# DoublePN-11092017-001.net
KiCad netlist of a schematic drawn in EAGLE
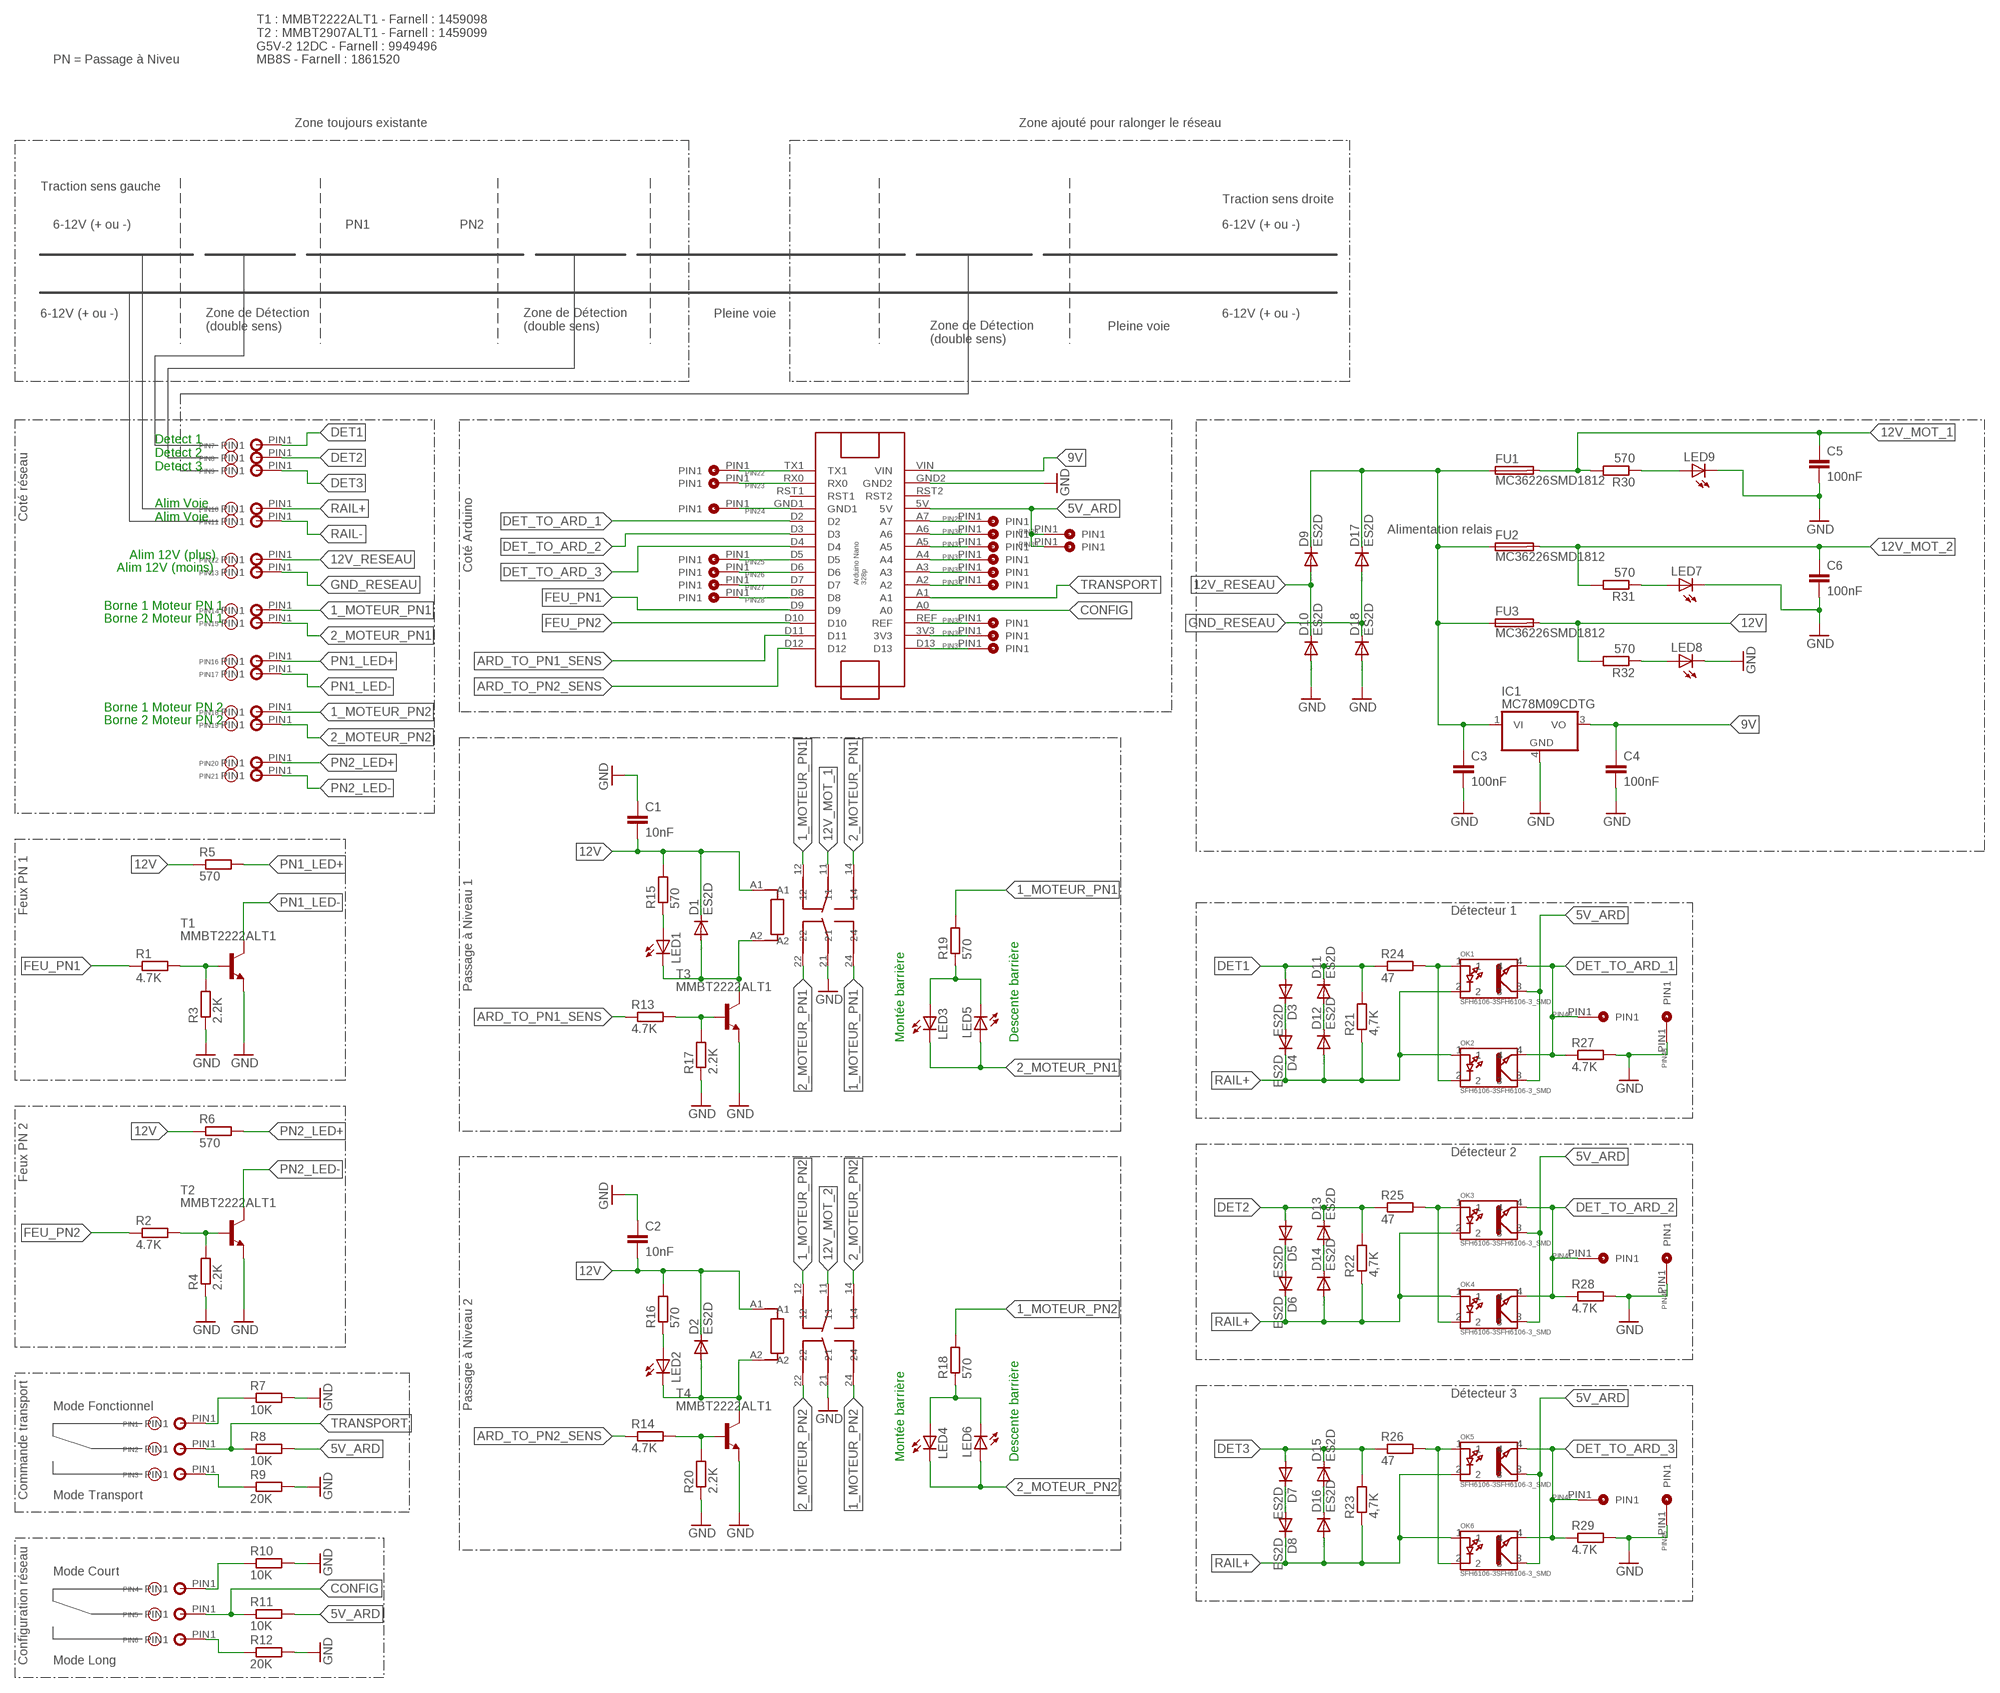
[diagram p0: schematic, sheet 1]

(export (version "E")
  (design (tool "Eeschema 10.0.6"))
  (components
    (comp (ref "ARDUINO-NANO1")
      (value "ARDUINO-NANO")
      (footprint "eagle-import:ARDUINO-NANO")
      (libsource (lib "eagle-import") (part "ARDUINO-NANO"))
    )
    (comp (ref "C1")
      (value "10nF")
      (footprint "eagle-import:C0805")
      (libsource (lib "eagle-import") (part "C-EUC0805"))
    )
    (comp (ref "C2")
      (value "10nF")
      (footprint "eagle-import:C0805")
      (libsource (lib "eagle-import") (part "C-EUC0805"))
    )
    (comp (ref "C3")
      (value "100nF")
      (footprint "eagle-import:C0805")
      (libsource (lib "eagle-import") (part "C-EUC0805"))
    )
    (comp (ref "C4")
      (value "100nF")
      (footprint "eagle-import:C0805")
      (libsource (lib "eagle-import") (part "C-EUC0805"))
    )
    (comp (ref "C5")
      (value "100nF")
      (footprint "eagle-import:C0805")
      (libsource (lib "eagle-import") (part "C-EUC0805"))
    )
    (comp (ref "C6")
      (value "100nF")
      (footprint "eagle-import:C0805")
      (libsource (lib "eagle-import") (part "C-EUC0805"))
    )
    (comp (ref "D1")
      (value "ES2D")
      (footprint "eagle-import:SMB")
      (libsource (lib "eagle-import") (part "ES2D"))
    )
    (comp (ref "D2")
      (value "ES2D")
      (footprint "eagle-import:SMB")
      (libsource (lib "eagle-import") (part "ES2D"))
    )
    (comp (ref "D3")
      (value "ES2D")
      (footprint "eagle-import:SMB")
      (libsource (lib "eagle-import") (part "ES2D"))
    )
    (comp (ref "D4")
      (value "ES2D")
      (footprint "eagle-import:SMB")
      (libsource (lib "eagle-import") (part "ES2D"))
    )
    (comp (ref "D5")
      (value "ES2D")
      (footprint "eagle-import:SMB")
      (libsource (lib "eagle-import") (part "ES2D"))
    )
    (comp (ref "D6")
      (value "ES2D")
      (footprint "eagle-import:SMB")
      (libsource (lib "eagle-import") (part "ES2D"))
    )
    (comp (ref "D7")
      (value "ES2D")
      (footprint "eagle-import:SMB")
      (libsource (lib "eagle-import") (part "ES2D"))
    )
    (comp (ref "D8")
      (value "ES2D")
      (footprint "eagle-import:SMB")
      (libsource (lib "eagle-import") (part "ES2D"))
    )
    (comp (ref "D9")
      (value "ES2D")
      (footprint "eagle-import:SMB")
      (libsource (lib "eagle-import") (part "ES2D"))
    )
    (comp (ref "D10")
      (value "ES2D")
      (footprint "eagle-import:SMB")
      (libsource (lib "eagle-import") (part "ES2D"))
    )
    (comp (ref "D11")
      (value "ES2D")
      (footprint "eagle-import:SMB")
      (libsource (lib "eagle-import") (part "ES2D"))
    )
    (comp (ref "D12")
      (value "ES2D")
      (footprint "eagle-import:SMB")
      (libsource (lib "eagle-import") (part "ES2D"))
    )
    (comp (ref "D13")
      (value "ES2D")
      (footprint "eagle-import:SMB")
      (libsource (lib "eagle-import") (part "ES2D"))
    )
    (comp (ref "D14")
      (value "ES2D")
      (footprint "eagle-import:SMB")
      (libsource (lib "eagle-import") (part "ES2D"))
    )
    (comp (ref "D15")
      (value "ES2D")
      (footprint "eagle-import:SMB")
      (libsource (lib "eagle-import") (part "ES2D"))
    )
    (comp (ref "D16")
      (value "ES2D")
      (footprint "eagle-import:SMB")
      (libsource (lib "eagle-import") (part "ES2D"))
    )
    (comp (ref "D17")
      (value "ES2D")
      (footprint "eagle-import:SMB")
      (libsource (lib "eagle-import") (part "ES2D"))
    )
    (comp (ref "D18")
      (value "ES2D")
      (footprint "eagle-import:SMB")
      (libsource (lib "eagle-import") (part "ES2D"))
    )
    (comp (ref "FU1")
      (value "MC36226SMD1812")
      (footprint "eagle-import:MC36226")
      (libsource (lib "eagle-import") (part "MC36226SMD1812"))
    )
    (comp (ref "FU2")
      (value "MC36226SMD1812")
      (footprint "eagle-import:MC36226")
      (libsource (lib "eagle-import") (part "MC36226SMD1812"))
    )
    (comp (ref "FU3")
      (value "MC36226SMD1812")
      (footprint "eagle-import:MC36226")
      (libsource (lib "eagle-import") (part "MC36226SMD1812"))
    )
    (comp (ref "IC1")
      (value "MC78M09CDTG")
      (footprint "eagle-import:DPACK_3")
      (libsource (lib "eagle-import") (part "MC78M09CDTG"))
    )
    (comp (ref "LED1")
      (value "LEDCHIPLED_0805")
      (footprint "eagle-import:CHIPLED_0805")
      (libsource (lib "eagle-import") (part "LEDCHIPLED_0805"))
    )
    (comp (ref "LED2")
      (value "LEDCHIPLED_0805")
      (footprint "eagle-import:CHIPLED_0805")
      (libsource (lib "eagle-import") (part "LEDCHIPLED_0805"))
    )
    (comp (ref "LED3")
      (value "LEDCHIPLED_0805")
      (footprint "eagle-import:CHIPLED_0805")
      (libsource (lib "eagle-import") (part "LEDCHIPLED_0805"))
    )
    (comp (ref "LED4")
      (value "LEDCHIPLED_0805")
      (footprint "eagle-import:CHIPLED_0805")
      (libsource (lib "eagle-import") (part "LEDCHIPLED_0805"))
    )
    (comp (ref "LED5")
      (value "LEDCHIPLED_0805")
      (footprint "eagle-import:CHIPLED_0805")
      (libsource (lib "eagle-import") (part "LEDCHIPLED_0805"))
    )
    (comp (ref "LED6")
      (value "LEDCHIPLED_0805")
      (footprint "eagle-import:CHIPLED_0805")
      (libsource (lib "eagle-import") (part "LEDCHIPLED_0805"))
    )
    (comp (ref "LED7")
      (value "LEDCHIPLED_0805")
      (footprint "eagle-import:CHIPLED_0805")
      (libsource (lib "eagle-import") (part "LEDCHIPLED_0805"))
    )
    (comp (ref "LED8")
      (value "LEDCHIPLED_0805")
      (footprint "eagle-import:CHIPLED_0805")
      (libsource (lib "eagle-import") (part "LEDCHIPLED_0805"))
    )
    (comp (ref "LED9")
      (value "LEDCHIPLED_0805")
      (footprint "eagle-import:CHIPLED_0805")
      (libsource (lib "eagle-import") (part "LEDCHIPLED_0805"))
    )
    (comp (ref "OK1")
      (value "SFH6106-3SFH6106-3_SMD")
      (footprint "eagle-import:SFH6106-3")
      (libsource (lib "eagle-import") (part "SFH6106-3SFH6106-3_SMD"))
    )
    (comp (ref "OK2")
      (value "SFH6106-3SFH6106-3_SMD")
      (footprint "eagle-import:SFH6106-3")
      (libsource (lib "eagle-import") (part "SFH6106-3SFH6106-3_SMD"))
    )
    (comp (ref "OK3")
      (value "SFH6106-3SFH6106-3_SMD")
      (footprint "eagle-import:SFH6106-3")
      (libsource (lib "eagle-import") (part "SFH6106-3SFH6106-3_SMD"))
    )
    (comp (ref "OK4")
      (value "SFH6106-3SFH6106-3_SMD")
      (footprint "eagle-import:SFH6106-3")
      (libsource (lib "eagle-import") (part "SFH6106-3SFH6106-3_SMD"))
    )
    (comp (ref "OK5")
      (value "SFH6106-3SFH6106-3_SMD")
      (footprint "eagle-import:SFH6106-3")
      (libsource (lib "eagle-import") (part "SFH6106-3SFH6106-3_SMD"))
    )
    (comp (ref "OK6")
      (value "SFH6106-3SFH6106-3_SMD")
      (footprint "eagle-import:SFH6106-3")
      (libsource (lib "eagle-import") (part "SFH6106-3SFH6106-3_SMD"))
    )
    (comp (ref "PIN1")
      (value "CON-FILTRAVERSANT-1FILTRAVERSANT-1")
      (footprint "eagle-import:CON-FILTRAVERSANT-1")
      (libsource (lib "eagle-import") (part "CON-FILTRAVERSANT-1FILTRAVERSANT-1"))
    )
    (comp (ref "PIN2")
      (value "CON-FILTRAVERSANT-1FILTRAVERSANT-1")
      (footprint "eagle-import:CON-FILTRAVERSANT-1")
      (libsource (lib "eagle-import") (part "CON-FILTRAVERSANT-1FILTRAVERSANT-1"))
    )
    (comp (ref "PIN3")
      (value "CON-FILTRAVERSANT-1FILTRAVERSANT-1")
      (footprint "eagle-import:CON-FILTRAVERSANT-1")
      (libsource (lib "eagle-import") (part "CON-FILTRAVERSANT-1FILTRAVERSANT-1"))
    )
    (comp (ref "PIN4")
      (value "CON-FILTRAVERSANT-1FILTRAVERSANT-1")
      (footprint "eagle-import:CON-FILTRAVERSANT-1")
      (libsource (lib "eagle-import") (part "CON-FILTRAVERSANT-1FILTRAVERSANT-1"))
    )
    (comp (ref "PIN5")
      (value "CON-FILTRAVERSANT-1FILTRAVERSANT-1")
      (footprint "eagle-import:CON-FILTRAVERSANT-1")
      (libsource (lib "eagle-import") (part "CON-FILTRAVERSANT-1FILTRAVERSANT-1"))
    )
    (comp (ref "PIN6")
      (value "CON-FILTRAVERSANT-1FILTRAVERSANT-1")
      (footprint "eagle-import:CON-FILTRAVERSANT-1")
      (libsource (lib "eagle-import") (part "CON-FILTRAVERSANT-1FILTRAVERSANT-1"))
    )
    (comp (ref "PIN7")
      (value "CON-FILTRAVERSANT-1FILTRAVERSANT-1")
      (footprint "eagle-import:CON-FILTRAVERSANT-1")
      (libsource (lib "eagle-import") (part "CON-FILTRAVERSANT-1FILTRAVERSANT-1"))
    )
    (comp (ref "PIN8")
      (value "CON-FILTRAVERSANT-1FILTRAVERSANT-1")
      (footprint "eagle-import:CON-FILTRAVERSANT-1")
      (libsource (lib "eagle-import") (part "CON-FILTRAVERSANT-1FILTRAVERSANT-1"))
    )
    (comp (ref "PIN9")
      (value "CON-FILTRAVERSANT-1FILTRAVERSANT-1")
      (footprint "eagle-import:CON-FILTRAVERSANT-1")
      (libsource (lib "eagle-import") (part "CON-FILTRAVERSANT-1FILTRAVERSANT-1"))
    )
    (comp (ref "PIN10")
      (value "CON-FILTRAVERSANT-1FILTRAVERSANT-1")
      (footprint "eagle-import:CON-FILTRAVERSANT-1")
      (libsource (lib "eagle-import") (part "CON-FILTRAVERSANT-1FILTRAVERSANT-1"))
    )
    (comp (ref "PIN11")
      (value "CON-FILTRAVERSANT-1FILTRAVERSANT-1")
      (footprint "eagle-import:CON-FILTRAVERSANT-1")
      (libsource (lib "eagle-import") (part "CON-FILTRAVERSANT-1FILTRAVERSANT-1"))
    )
    (comp (ref "PIN12")
      (value "CON-FILTRAVERSANT-1FILTRAVERSANT-1")
      (footprint "eagle-import:CON-FILTRAVERSANT-1")
      (libsource (lib "eagle-import") (part "CON-FILTRAVERSANT-1FILTRAVERSANT-1"))
    )
    (comp (ref "PIN13")
      (value "CON-FILTRAVERSANT-1FILTRAVERSANT-1")
      (footprint "eagle-import:CON-FILTRAVERSANT-1")
      (libsource (lib "eagle-import") (part "CON-FILTRAVERSANT-1FILTRAVERSANT-1"))
    )
    (comp (ref "PIN14")
      (value "CON-FILTRAVERSANT-1FILTRAVERSANT-1")
      (footprint "eagle-import:CON-FILTRAVERSANT-1")
      (libsource (lib "eagle-import") (part "CON-FILTRAVERSANT-1FILTRAVERSANT-1"))
    )
    (comp (ref "PIN15")
      (value "CON-FILTRAVERSANT-1FILTRAVERSANT-1")
      (footprint "eagle-import:CON-FILTRAVERSANT-1")
      (libsource (lib "eagle-import") (part "CON-FILTRAVERSANT-1FILTRAVERSANT-1"))
    )
    (comp (ref "PIN16")
      (value "CON-FILTRAVERSANT-1FILTRAVERSANT-1")
      (footprint "eagle-import:CON-FILTRAVERSANT-1")
      (libsource (lib "eagle-import") (part "CON-FILTRAVERSANT-1FILTRAVERSANT-1"))
    )
    (comp (ref "PIN17")
      (value "CON-FILTRAVERSANT-1FILTRAVERSANT-1")
      (footprint "eagle-import:CON-FILTRAVERSANT-1")
      (libsource (lib "eagle-import") (part "CON-FILTRAVERSANT-1FILTRAVERSANT-1"))
    )
    (comp (ref "PIN18")
      (value "CON-FILTRAVERSANT-1FILTRAVERSANT-1")
      (footprint "eagle-import:CON-FILTRAVERSANT-1")
      (libsource (lib "eagle-import") (part "CON-FILTRAVERSANT-1FILTRAVERSANT-1"))
    )
    (comp (ref "PIN19")
      (value "CON-FILTRAVERSANT-1FILTRAVERSANT-1")
      (footprint "eagle-import:CON-FILTRAVERSANT-1")
      (libsource (lib "eagle-import") (part "CON-FILTRAVERSANT-1FILTRAVERSANT-1"))
    )
    (comp (ref "PIN20")
      (value "CON-FILTRAVERSANT-1FILTRAVERSANT-1")
      (footprint "eagle-import:CON-FILTRAVERSANT-1")
      (libsource (lib "eagle-import") (part "CON-FILTRAVERSANT-1FILTRAVERSANT-1"))
    )
    (comp (ref "PIN21")
      (value "CON-FILTRAVERSANT-1FILTRAVERSANT-1")
      (footprint "eagle-import:CON-FILTRAVERSANT-1")
      (libsource (lib "eagle-import") (part "CON-FILTRAVERSANT-1FILTRAVERSANT-1"))
    )
    (comp (ref "PIN22")
      (value "CON-TRAV-1PIN")
      (footprint "eagle-import:CON-TRAV-1")
      (libsource (lib "eagle-import") (part "CON-TRAV-1PIN"))
    )
    (comp (ref "PIN23")
      (value "CON-TRAV-1PIN")
      (footprint "eagle-import:CON-TRAV-1")
      (libsource (lib "eagle-import") (part "CON-TRAV-1PIN"))
    )
    (comp (ref "PIN24")
      (value "CON-TRAV-1PIN")
      (footprint "eagle-import:CON-TRAV-1")
      (libsource (lib "eagle-import") (part "CON-TRAV-1PIN"))
    )
    (comp (ref "PIN25")
      (value "CON-TRAV-1PIN")
      (footprint "eagle-import:CON-TRAV-1")
      (libsource (lib "eagle-import") (part "CON-TRAV-1PIN"))
    )
    (comp (ref "PIN26")
      (value "CON-TRAV-1PIN")
      (footprint "eagle-import:CON-TRAV-1")
      (libsource (lib "eagle-import") (part "CON-TRAV-1PIN"))
    )
    (comp (ref "PIN27")
      (value "CON-TRAV-1PIN")
      (footprint "eagle-import:CON-TRAV-1")
      (libsource (lib "eagle-import") (part "CON-TRAV-1PIN"))
    )
    (comp (ref "PIN28")
      (value "CON-TRAV-1PIN")
      (footprint "eagle-import:CON-TRAV-1")
      (libsource (lib "eagle-import") (part "CON-TRAV-1PIN"))
    )
    (comp (ref "PIN29")
      (value "CON-TRAV-1PIN")
      (footprint "eagle-import:CON-TRAV-1")
      (libsource (lib "eagle-import") (part "CON-TRAV-1PIN"))
    )
    (comp (ref "PIN30")
      (value "CON-TRAV-1PIN")
      (footprint "eagle-import:CON-TRAV-1")
      (libsource (lib "eagle-import") (part "CON-TRAV-1PIN"))
    )
    (comp (ref "PIN31")
      (value "CON-TRAV-1PIN")
      (footprint "eagle-import:CON-TRAV-1")
      (libsource (lib "eagle-import") (part "CON-TRAV-1PIN"))
    )
    (comp (ref "PIN32")
      (value "CON-TRAV-1PIN")
      (footprint "eagle-import:CON-TRAV-1")
      (libsource (lib "eagle-import") (part "CON-TRAV-1PIN"))
    )
    (comp (ref "PIN33")
      (value "CON-TRAV-1PIN")
      (footprint "eagle-import:CON-TRAV-1")
      (libsource (lib "eagle-import") (part "CON-TRAV-1PIN"))
    )
    (comp (ref "PIN34")
      (value "CON-TRAV-1PIN")
      (footprint "eagle-import:CON-TRAV-1")
      (libsource (lib "eagle-import") (part "CON-TRAV-1PIN"))
    )
    (comp (ref "PIN35")
      (value "CON-TRAV-1PIN")
      (footprint "eagle-import:CON-TRAV-1")
      (libsource (lib "eagle-import") (part "CON-TRAV-1PIN"))
    )
    (comp (ref "PIN36")
      (value "CON-TRAV-1PIN")
      (footprint "eagle-import:CON-TRAV-1")
      (libsource (lib "eagle-import") (part "CON-TRAV-1PIN"))
    )
    (comp (ref "PIN37")
      (value "CON-TRAV-1PIN")
      (footprint "eagle-import:CON-TRAV-1")
      (libsource (lib "eagle-import") (part "CON-TRAV-1PIN"))
    )
    (comp (ref "PIN38")
      (value "CON-TRAV-1PIN")
      (footprint "eagle-import:CON-TRAV-1")
      (libsource (lib "eagle-import") (part "CON-TRAV-1PIN"))
    )
    (comp (ref "PIN39")
      (value "CON-TRAV-1PIN")
      (footprint "eagle-import:CON-TRAV-1")
      (libsource (lib "eagle-import") (part "CON-TRAV-1PIN"))
    )
    (comp (ref "PIN40")
      (value "CON-TRAV-1PIN")
      (footprint "eagle-import:CON-TRAV-1")
      (libsource (lib "eagle-import") (part "CON-TRAV-1PIN"))
    )
    (comp (ref "PIN41")
      (value "CON-TRAV-1PIN")
      (footprint "eagle-import:CON-TRAV-1")
      (libsource (lib "eagle-import") (part "CON-TRAV-1PIN"))
    )
    (comp (ref "PIN42")
      (value "CON-TRAV-1PIN")
      (footprint "eagle-import:CON-TRAV-1")
      (libsource (lib "eagle-import") (part "CON-TRAV-1PIN"))
    )
    (comp (ref "PIN43")
      (value "CON-TRAV-1PIN")
      (footprint "eagle-import:CON-TRAV-1")
      (libsource (lib "eagle-import") (part "CON-TRAV-1PIN"))
    )
    (comp (ref "PIN44")
      (value "CON-TRAV-1PIN")
      (footprint "eagle-import:CON-TRAV-1")
      (libsource (lib "eagle-import") (part "CON-TRAV-1PIN"))
    )
    (comp (ref "PIN45")
      (value "CON-TRAV-1PIN")
      (footprint "eagle-import:CON-TRAV-1")
      (libsource (lib "eagle-import") (part "CON-TRAV-1PIN"))
    )
    (comp (ref "R1")
      (value "4.7K")
      (footprint "eagle-import:R0805")
      (libsource (lib "eagle-import") (part "R-EU_R0805"))
    )
    (comp (ref "R2")
      (value "4.7K")
      (footprint "eagle-import:R0805")
      (libsource (lib "eagle-import") (part "R-EU_R0805"))
    )
    (comp (ref "R3")
      (value "2.2K")
      (footprint "eagle-import:R0805")
      (libsource (lib "eagle-import") (part "R-EU_R0805"))
    )
    (comp (ref "R4")
      (value "2.2K")
      (footprint "eagle-import:R0805")
      (libsource (lib "eagle-import") (part "R-EU_R0805"))
    )
    (comp (ref "R5")
      (value "570")
      (footprint "eagle-import:R0805")
      (libsource (lib "eagle-import") (part "R-EU_R0805"))
    )
    (comp (ref "R6")
      (value "570")
      (footprint "eagle-import:R0805")
      (libsource (lib "eagle-import") (part "R-EU_R0805"))
    )
    (comp (ref "R7")
      (value "10K")
      (footprint "eagle-import:R0805")
      (libsource (lib "eagle-import") (part "R-EU_R0805"))
    )
    (comp (ref "R8")
      (value "10K")
      (footprint "eagle-import:R0805")
      (libsource (lib "eagle-import") (part "R-EU_R0805"))
    )
    (comp (ref "R9")
      (value "20K")
      (footprint "eagle-import:R0805")
      (libsource (lib "eagle-import") (part "R-EU_R0805"))
    )
    (comp (ref "R10")
      (value "10K")
      (footprint "eagle-import:R0805")
      (libsource (lib "eagle-import") (part "R-EU_R0805"))
    )
    (comp (ref "R11")
      (value "10K")
      (footprint "eagle-import:R0805")
      (libsource (lib "eagle-import") (part "R-EU_R0805"))
    )
    (comp (ref "R12")
      (value "20K")
      (footprint "eagle-import:R0805")
      (libsource (lib "eagle-import") (part "R-EU_R0805"))
    )
    (comp (ref "R13")
      (value "4.7K")
      (footprint "eagle-import:R0805")
      (libsource (lib "eagle-import") (part "R-EU_R0805"))
    )
    (comp (ref "R14")
      (value "4.7K")
      (footprint "eagle-import:R0805")
      (libsource (lib "eagle-import") (part "R-EU_R0805"))
    )
    (comp (ref "R15")
      (value "570")
      (footprint "eagle-import:R0805")
      (libsource (lib "eagle-import") (part "R-EU_R0805"))
    )
    (comp (ref "R16")
      (value "570")
      (footprint "eagle-import:R0805")
      (libsource (lib "eagle-import") (part "R-EU_R0805"))
    )
    (comp (ref "R17")
      (value "2.2K")
      (footprint "eagle-import:R0805")
      (libsource (lib "eagle-import") (part "R-EU_R0805"))
    )
    (comp (ref "R18")
      (value "570")
      (footprint "eagle-import:R0805")
      (libsource (lib "eagle-import") (part "R-EU_R0805"))
    )
    (comp (ref "R19")
      (value "570")
      (footprint "eagle-import:R0805")
      (libsource (lib "eagle-import") (part "R-EU_R0805"))
    )
    (comp (ref "R20")
      (value "2.2K")
      (footprint "eagle-import:R0805")
      (libsource (lib "eagle-import") (part "R-EU_R0805"))
    )
    (comp (ref "R21")
      (value "4,7K")
      (footprint "eagle-import:R0805")
      (libsource (lib "eagle-import") (part "R-EU_R0805"))
    )
    (comp (ref "R22")
      (value "4,7K")
      (footprint "eagle-import:R0805")
      (libsource (lib "eagle-import") (part "R-EU_R0805"))
    )
    (comp (ref "R23")
      (value "4,7K")
      (footprint "eagle-import:R0805")
      (libsource (lib "eagle-import") (part "R-EU_R0805"))
    )
    (comp (ref "R24")
      (value "47")
      (footprint "eagle-import:R0805")
      (libsource (lib "eagle-import") (part "R-EU_R0805"))
    )
    (comp (ref "R25")
      (value "47")
      (footprint "eagle-import:R0805")
      (libsource (lib "eagle-import") (part "R-EU_R0805"))
    )
    (comp (ref "R26")
      (value "47")
      (footprint "eagle-import:R0805")
      (libsource (lib "eagle-import") (part "R-EU_R0805"))
    )
    (comp (ref "R27")
      (value "4.7K")
      (footprint "eagle-import:R0805")
      (libsource (lib "eagle-import") (part "R-EU_R0805"))
    )
    (comp (ref "R28")
      (value "4.7K")
      (footprint "eagle-import:R0805")
      (libsource (lib "eagle-import") (part "R-EU_R0805"))
    )
    (comp (ref "R29")
      (value "4.7K")
      (footprint "eagle-import:R0805")
      (libsource (lib "eagle-import") (part "R-EU_R0805"))
    )
    (comp (ref "R30")
      (value "570")
      (footprint "eagle-import:R0805")
      (libsource (lib "eagle-import") (part "R-EU_R0805"))
    )
    (comp (ref "R31")
      (value "570")
      (footprint "eagle-import:R0805")
      (libsource (lib "eagle-import") (part "R-EU_R0805"))
    )
    (comp (ref "R32")
      (value "570")
      (footprint "eagle-import:R0805")
      (libsource (lib "eagle-import") (part "R-EU_R0805"))
    )
    (comp (ref "RLS1")
      (value "FINDER-DPDT-12VFINDER-DPDT-12V")
      (footprint "eagle-import:FINDER-DPDT-12V")
      (libsource (lib "eagle-import") (part "FINDER-DPDT-12VFINDER-DPDT-12V"))
    )
    (comp (ref "RLS2")
      (value "FINDER-DPDT-12VFINDER-DPDT-12V")
      (footprint "eagle-import:FINDER-DPDT-12V")
      (libsource (lib "eagle-import") (part "FINDER-DPDT-12VFINDER-DPDT-12V"))
    )
    (comp (ref "T1")
      (value "MMBT2222ALT1")
      (footprint "eagle-import:SOT23-BEC")
      (libsource (lib "eagle-import") (part "-NPN-SOT23-BECMMBT2222ALT1"))
    )
    (comp (ref "T2")
      (value "MMBT2222ALT1")
      (footprint "eagle-import:SOT23-BEC")
      (libsource (lib "eagle-import") (part "-NPN-SOT23-BECMMBT2222ALT1"))
    )
    (comp (ref "T3")
      (value "MMBT2222ALT1")
      (footprint "eagle-import:SOT23-BEC")
      (libsource (lib "eagle-import") (part "-NPN-SOT23-BECMMBT2222ALT1"))
    )
    (comp (ref "T4")
      (value "MMBT2222ALT1")
      (footprint "eagle-import:SOT23-BEC")
      (libsource (lib "eagle-import") (part "-NPN-SOT23-BECMMBT2222ALT1"))
    )
  )
  (nets
    (net (code "1") (name "1_MOTEUR_PN1") (class "Default")
      (node (ref "PIN14") (pin "PIN1") (pinfunction "PIN1_PIN1") (pintype "bidirectional"))
      (node (ref "R19") (pin "2") (pinfunction "2_2") (pintype "passive"))
      (node (ref "RLS1") (pin "12") (pinfunction "12_12") (pintype "bidirectional"))
      (node (ref "RLS1") (pin "24") (pinfunction "24_24") (pintype "bidirectional"))
    )
    (net (code "2") (name "1_MOTEUR_PN2") (class "Default")
      (node (ref "PIN18") (pin "PIN1") (pinfunction "PIN1_PIN1") (pintype "bidirectional"))
      (node (ref "R18") (pin "2") (pinfunction "2_2") (pintype "passive"))
      (node (ref "RLS2") (pin "12") (pinfunction "12_12") (pintype "bidirectional"))
      (node (ref "RLS2") (pin "24") (pinfunction "24_24") (pintype "bidirectional"))
    )
    (net (code "3") (name "2_MOTEUR_PN1") (class "Default")
      (node (ref "LED3") (pin "C") (pinfunction "C_C") (pintype "passive"))
      (node (ref "LED5") (pin "A") (pinfunction "A_A") (pintype "passive"))
      (node (ref "PIN15") (pin "PIN1") (pinfunction "PIN1_PIN1") (pintype "bidirectional"))
      (node (ref "RLS1") (pin "14") (pinfunction "14_14") (pintype "bidirectional"))
      (node (ref "RLS1") (pin "22") (pinfunction "22_22") (pintype "bidirectional"))
    )
    (net (code "4") (name "2_MOTEUR_PN2") (class "Default")
      (node (ref "LED4") (pin "C") (pinfunction "C_C") (pintype "passive"))
      (node (ref "LED6") (pin "A") (pinfunction "A_A") (pintype "passive"))
      (node (ref "PIN19") (pin "PIN1") (pinfunction "PIN1_PIN1") (pintype "bidirectional"))
      (node (ref "RLS2") (pin "14") (pinfunction "14_14") (pintype "bidirectional"))
      (node (ref "RLS2") (pin "22") (pinfunction "22_22") (pintype "bidirectional"))
    )
    (net (code "5") (name "5V_ARD") (class "Default")
      (node (ref "ARDUINO-NANO1") (pin "5V") (pinfunction "5V_5V") (pintype "bidirectional"))
      (node (ref "OK1") (pin "3") (pinfunction "3_3") (pintype "bidirectional"))
      (node (ref "OK2") (pin "3") (pinfunction "3_3") (pintype "bidirectional"))
      (node (ref "OK3") (pin "3") (pinfunction "3_3") (pintype "bidirectional"))
      (node (ref "OK4") (pin "3") (pinfunction "3_3") (pintype "bidirectional"))
      (node (ref "OK5") (pin "3") (pinfunction "3_3") (pintype "bidirectional"))
      (node (ref "OK6") (pin "3") (pinfunction "3_3") (pintype "bidirectional"))
      (node (ref "PIN38") (pin "PIN1") (pinfunction "PIN1_PIN1") (pintype "bidirectional"))
      (node (ref "PIN39") (pin "PIN1") (pinfunction "PIN1_PIN1") (pintype "bidirectional"))
      (node (ref "R11") (pin "2") (pinfunction "2_2") (pintype "passive"))
      (node (ref "R8") (pin "2") (pinfunction "2_2") (pintype "passive"))
    )
    (net (code "6") (name "9V") (class "Default")
      (node (ref "ARDUINO-NANO1") (pin "VIN") (pinfunction "VIN_VIN") (pintype "input"))
      (node (ref "C4") (pin "1") (pinfunction "1_1") (pintype "passive"))
      (node (ref "IC1") (pin "3") (pinfunction "VO_3") (pintype "passive"))
    )
    (net (code "7") (name "12V") (class "Default")
      (node (ref "C1") (pin "2") (pinfunction "2_2") (pintype "passive"))
      (node (ref "C2") (pin "2") (pinfunction "2_2") (pintype "passive"))
      (node (ref "D1") (pin "C") (pinfunction "C_C") (pintype "passive"))
      (node (ref "D2") (pin "C") (pinfunction "C_C") (pintype "passive"))
      (node (ref "FU3") (pin "2") (pinfunction "2_2") (pintype "passive"))
      (node (ref "R15") (pin "2") (pinfunction "2_2") (pintype "passive"))
      (node (ref "R16") (pin "2") (pinfunction "2_2") (pintype "passive"))
      (node (ref "R32") (pin "2") (pinfunction "2_2") (pintype "passive"))
      (node (ref "R5") (pin "1") (pinfunction "1_1") (pintype "passive"))
      (node (ref "R6") (pin "1") (pinfunction "1_1") (pintype "passive"))
      (node (ref "RLS1") (pin "A1") (pinfunction "A1_A1") (pintype "bidirectional"))
      (node (ref "RLS2") (pin "A1") (pinfunction "A1_A1") (pintype "bidirectional"))
    )
    (net (code "8") (name "12V_MOT_1") (class "Default")
      (node (ref "C5") (pin "1") (pinfunction "1_1") (pintype "passive"))
      (node (ref "FU1") (pin "2") (pinfunction "2_2") (pintype "passive"))
      (node (ref "R30") (pin "2") (pinfunction "2_2") (pintype "passive"))
      (node (ref "RLS1") (pin "11") (pinfunction "11_11") (pintype "bidirectional"))
    )
    (net (code "9") (name "12V_MOT_2") (class "Default")
      (node (ref "C6") (pin "1") (pinfunction "1_1") (pintype "passive"))
      (node (ref "FU2") (pin "2") (pinfunction "2_2") (pintype "passive"))
      (node (ref "R31") (pin "2") (pinfunction "2_2") (pintype "passive"))
      (node (ref "RLS2") (pin "11") (pinfunction "11_11") (pintype "bidirectional"))
    )
    (net (code "10") (name "12V_RESEAU") (class "Default")
      (node (ref "D10") (pin "C") (pinfunction "C_C") (pintype "passive"))
      (node (ref "D9") (pin "A") (pinfunction "A_A") (pintype "passive"))
      (node (ref "PIN12") (pin "PIN1") (pinfunction "PIN1_PIN1") (pintype "bidirectional"))
    )
    (net (code "11") (name "ARD_TO_PN1_SENS") (class "Default")
      (node (ref "ARDUINO-NANO1") (pin "D11") (pinfunction "D11_D11") (pintype "bidirectional"))
      (node (ref "R13") (pin "1") (pinfunction "1_1") (pintype "passive"))
    )
    (net (code "12") (name "ARD_TO_PN2_SENS") (class "Default")
      (node (ref "ARDUINO-NANO1") (pin "D12") (pinfunction "D12_D12") (pintype "bidirectional"))
      (node (ref "R14") (pin "1") (pinfunction "1_1") (pintype "passive"))
    )
    (net (code "13") (name "CONFIG") (class "Default")
      (node (ref "ARDUINO-NANO1") (pin "A0") (pinfunction "A0_A0") (pintype "bidirectional"))
      (node (ref "PIN5") (pin "PIN1") (pinfunction "PIN1_PIN1") (pintype "bidirectional"))
      (node (ref "R11") (pin "1") (pinfunction "1_1") (pintype "passive"))
    )
    (net (code "14") (name "DET1") (class "Default")
      (node (ref "D11") (pin "C") (pinfunction "C_C") (pintype "passive"))
      (node (ref "D3") (pin "A") (pinfunction "A_A") (pintype "passive"))
      (node (ref "PIN7") (pin "PIN1") (pinfunction "PIN1_PIN1") (pintype "bidirectional"))
      (node (ref "R21") (pin "2") (pinfunction "2_2") (pintype "passive"))
      (node (ref "R24") (pin "1") (pinfunction "1_1") (pintype "passive"))
    )
    (net (code "15") (name "DET2") (class "Default")
      (node (ref "D13") (pin "C") (pinfunction "C_C") (pintype "passive"))
      (node (ref "D5") (pin "A") (pinfunction "A_A") (pintype "passive"))
      (node (ref "PIN8") (pin "PIN1") (pinfunction "PIN1_PIN1") (pintype "bidirectional"))
      (node (ref "R22") (pin "2") (pinfunction "2_2") (pintype "passive"))
      (node (ref "R25") (pin "1") (pinfunction "1_1") (pintype "passive"))
    )
    (net (code "16") (name "DET3") (class "Default")
      (node (ref "D15") (pin "C") (pinfunction "C_C") (pintype "passive"))
      (node (ref "D7") (pin "A") (pinfunction "A_A") (pintype "passive"))
      (node (ref "PIN9") (pin "PIN1") (pinfunction "PIN1_PIN1") (pintype "bidirectional"))
      (node (ref "R23") (pin "2") (pinfunction "2_2") (pintype "passive"))
      (node (ref "R26") (pin "1") (pinfunction "1_1") (pintype "passive"))
    )
    (net (code "17") (name "DET_TO_ARD_1") (class "Default")
      (node (ref "ARDUINO-NANO1") (pin "D2") (pinfunction "D2_D2") (pintype "bidirectional"))
      (node (ref "OK1") (pin "4") (pinfunction "4_4") (pintype "bidirectional"))
      (node (ref "OK2") (pin "4") (pinfunction "4_4") (pintype "bidirectional"))
      (node (ref "PIN40") (pin "PIN1") (pinfunction "PIN1_PIN1") (pintype "bidirectional"))
      (node (ref "R27") (pin "1") (pinfunction "1_1") (pintype "passive"))
    )
    (net (code "18") (name "DET_TO_ARD_2") (class "Default")
      (node (ref "ARDUINO-NANO1") (pin "D3") (pinfunction "D3_D3") (pintype "bidirectional"))
      (node (ref "OK3") (pin "4") (pinfunction "4_4") (pintype "bidirectional"))
      (node (ref "OK4") (pin "4") (pinfunction "4_4") (pintype "bidirectional"))
      (node (ref "PIN41") (pin "PIN1") (pinfunction "PIN1_PIN1") (pintype "bidirectional"))
      (node (ref "R28") (pin "1") (pinfunction "1_1") (pintype "passive"))
    )
    (net (code "19") (name "DET_TO_ARD_3") (class "Default")
      (node (ref "ARDUINO-NANO1") (pin "D4") (pinfunction "D4_D4") (pintype "bidirectional"))
      (node (ref "OK5") (pin "4") (pinfunction "4_4") (pintype "bidirectional"))
      (node (ref "OK6") (pin "4") (pinfunction "4_4") (pintype "bidirectional"))
      (node (ref "PIN42") (pin "PIN1") (pinfunction "PIN1_PIN1") (pintype "bidirectional"))
      (node (ref "R29") (pin "1") (pinfunction "1_1") (pintype "passive"))
    )
    (net (code "20") (name "FEU_PN1") (class "Default")
      (node (ref "ARDUINO-NANO1") (pin "D9") (pinfunction "D9_D9") (pintype "bidirectional"))
      (node (ref "R1") (pin "1") (pinfunction "1_1") (pintype "passive"))
    )
    (net (code "21") (name "FEU_PN2") (class "Default")
      (node (ref "ARDUINO-NANO1") (pin "D10") (pinfunction "D10_D10") (pintype "bidirectional"))
      (node (ref "R2") (pin "1") (pinfunction "1_1") (pintype "passive"))
    )
    (net (code "22") (name "GND") (class "Default")
      (node (ref "ARDUINO-NANO1") (pin "GND2") (pinfunction "GND2_GND2") (pintype "bidirectional"))
      (node (ref "C1") (pin "1") (pinfunction "1_1") (pintype "passive"))
      (node (ref "C2") (pin "1") (pinfunction "1_1") (pintype "passive"))
      (node (ref "C3") (pin "2") (pinfunction "2_2") (pintype "passive"))
      (node (ref "C4") (pin "2") (pinfunction "2_2") (pintype "passive"))
      (node (ref "C5") (pin "2") (pinfunction "2_2") (pintype "passive"))
      (node (ref "C6") (pin "2") (pinfunction "2_2") (pintype "passive"))
      (node (ref "D10") (pin "A") (pinfunction "A_A") (pintype "passive"))
      (node (ref "D18") (pin "A") (pinfunction "A_A") (pintype "passive"))
      (node (ref "IC1") (pin "4") (pinfunction "GND_4") (pintype "passive"))
      (node (ref "LED7") (pin "C") (pinfunction "C_C") (pintype "passive"))
      (node (ref "LED8") (pin "C") (pinfunction "C_C") (pintype "passive"))
      (node (ref "LED9") (pin "C") (pinfunction "C_C") (pintype "passive"))
      (node (ref "PIN43") (pin "PIN1") (pinfunction "PIN1_PIN1") (pintype "bidirectional"))
      (node (ref "PIN44") (pin "PIN1") (pinfunction "PIN1_PIN1") (pintype "bidirectional"))
      (node (ref "PIN45") (pin "PIN1") (pinfunction "PIN1_PIN1") (pintype "bidirectional"))
      (node (ref "R10") (pin "2") (pinfunction "2_2") (pintype "passive"))
      (node (ref "R12") (pin "2") (pinfunction "2_2") (pintype "passive"))
      (node (ref "R17") (pin "1") (pinfunction "1_1") (pintype "passive"))
      (node (ref "R20") (pin "1") (pinfunction "1_1") (pintype "passive"))
      (node (ref "R27") (pin "2") (pinfunction "2_2") (pintype "passive"))
      (node (ref "R28") (pin "2") (pinfunction "2_2") (pintype "passive"))
      (node (ref "R29") (pin "2") (pinfunction "2_2") (pintype "passive"))
      (node (ref "R3") (pin "1") (pinfunction "1_1") (pintype "passive"))
      (node (ref "R4") (pin "1") (pinfunction "1_1") (pintype "passive"))
      (node (ref "R7") (pin "2") (pinfunction "2_2") (pintype "passive"))
      (node (ref "R9") (pin "2") (pinfunction "2_2") (pintype "passive"))
      (node (ref "RLS1") (pin "21") (pinfunction "21_21") (pintype "bidirectional"))
      (node (ref "RLS2") (pin "21") (pinfunction "21_21") (pintype "bidirectional"))
      (node (ref "T1") (pin "E") (pinfunction "E_E") (pintype "passive"))
      (node (ref "T2") (pin "E") (pinfunction "E_E") (pintype "passive"))
      (node (ref "T3") (pin "E") (pinfunction "E_E") (pintype "passive"))
      (node (ref "T4") (pin "E") (pinfunction "E_E") (pintype "passive"))
    )
    (net (code "23") (name "GND_RESEAU") (class "Default")
      (node (ref "D17") (pin "A") (pinfunction "A_A") (pintype "passive"))
      (node (ref "D18") (pin "C") (pinfunction "C_C") (pintype "passive"))
      (node (ref "PIN13") (pin "PIN1") (pinfunction "PIN1_PIN1") (pintype "bidirectional"))
    )
    (net (code "24") (name "Net-(ARDUINO-NANO1-Pad3V3)") (class "Default")
      (node (ref "ARDUINO-NANO1") (pin "3V3") (pinfunction "3V3_3V3") (pintype "output"))
      (node (ref "PIN36") (pin "PIN1") (pinfunction "PIN1_PIN1") (pintype "bidirectional"))
    )
    (net (code "25") (name "Net-(ARDUINO-NANO1-PadA2)") (class "Default")
      (node (ref "ARDUINO-NANO1") (pin "A2") (pinfunction "A2_A2") (pintype "bidirectional"))
      (node (ref "PIN34") (pin "PIN1") (pinfunction "PIN1_PIN1") (pintype "bidirectional"))
    )
    (net (code "26") (name "Net-(ARDUINO-NANO1-PadA3)") (class "Default")
      (node (ref "ARDUINO-NANO1") (pin "A3") (pinfunction "A3_A3") (pintype "bidirectional"))
      (node (ref "PIN33") (pin "PIN1") (pinfunction "PIN1_PIN1") (pintype "bidirectional"))
    )
    (net (code "27") (name "Net-(ARDUINO-NANO1-PadA4)") (class "Default")
      (node (ref "ARDUINO-NANO1") (pin "A4") (pinfunction "A4_A4") (pintype "bidirectional"))
      (node (ref "PIN32") (pin "PIN1") (pinfunction "PIN1_PIN1") (pintype "bidirectional"))
    )
    (net (code "28") (name "Net-(ARDUINO-NANO1-PadA5)") (class "Default")
      (node (ref "ARDUINO-NANO1") (pin "A5") (pinfunction "A5_A5") (pintype "bidirectional"))
      (node (ref "PIN31") (pin "PIN1") (pinfunction "PIN1_PIN1") (pintype "bidirectional"))
    )
    (net (code "29") (name "Net-(ARDUINO-NANO1-PadA6)") (class "Default")
      (node (ref "ARDUINO-NANO1") (pin "A6") (pinfunction "A6_A6") (pintype "bidirectional"))
      (node (ref "PIN30") (pin "PIN1") (pinfunction "PIN1_PIN1") (pintype "bidirectional"))
    )
    (net (code "30") (name "Net-(ARDUINO-NANO1-PadA7)") (class "Default")
      (node (ref "ARDUINO-NANO1") (pin "A7") (pinfunction "A7_A7") (pintype "output"))
      (node (ref "PIN29") (pin "PIN1") (pinfunction "PIN1_PIN1") (pintype "bidirectional"))
    )
    (net (code "31") (name "Net-(ARDUINO-NANO1-PadD5)") (class "Default")
      (node (ref "ARDUINO-NANO1") (pin "D5") (pinfunction "D5_D5") (pintype "bidirectional"))
      (node (ref "PIN25") (pin "PIN1") (pinfunction "PIN1_PIN1") (pintype "bidirectional"))
    )
    (net (code "32") (name "Net-(ARDUINO-NANO1-PadD6)") (class "Default")
      (node (ref "ARDUINO-NANO1") (pin "D6") (pinfunction "D6_D6") (pintype "bidirectional"))
      (node (ref "PIN26") (pin "PIN1") (pinfunction "PIN1_PIN1") (pintype "bidirectional"))
    )
    (net (code "33") (name "Net-(ARDUINO-NANO1-PadD7)") (class "Default")
      (node (ref "ARDUINO-NANO1") (pin "D7") (pinfunction "D7_D7") (pintype "bidirectional"))
      (node (ref "PIN27") (pin "PIN1") (pinfunction "PIN1_PIN1") (pintype "bidirectional"))
    )
    (net (code "34") (name "Net-(ARDUINO-NANO1-PadD8)") (class "Default")
      (node (ref "ARDUINO-NANO1") (pin "D8") (pinfunction "D8_D8") (pintype "bidirectional"))
      (node (ref "PIN28") (pin "PIN1") (pinfunction "PIN1_PIN1") (pintype "bidirectional"))
    )
    (net (code "35") (name "Net-(ARDUINO-NANO1-PadD13)") (class "Default")
      (node (ref "ARDUINO-NANO1") (pin "D13") (pinfunction "D13_D13") (pintype "bidirectional"))
      (node (ref "PIN37") (pin "PIN1") (pinfunction "PIN1_PIN1") (pintype "bidirectional"))
    )
    (net (code "36") (name "Net-(ARDUINO-NANO1-PadGND1)") (class "Default")
      (node (ref "ARDUINO-NANO1") (pin "GND1") (pinfunction "GND1_GND1") (pintype "input"))
      (node (ref "PIN24") (pin "PIN1") (pinfunction "PIN1_PIN1") (pintype "bidirectional"))
    )
    (net (code "37") (name "Net-(ARDUINO-NANO1-PadREF)") (class "Default")
      (node (ref "ARDUINO-NANO1") (pin "REF") (pinfunction "REF_REF") (pintype "output"))
      (node (ref "PIN35") (pin "PIN1") (pinfunction "PIN1_PIN1") (pintype "bidirectional"))
    )
    (net (code "38") (name "Net-(ARDUINO-NANO1-PadRX0)") (class "Default")
      (node (ref "ARDUINO-NANO1") (pin "RX0") (pinfunction "RX0_RX0") (pintype "input"))
      (node (ref "PIN23") (pin "PIN1") (pinfunction "PIN1_PIN1") (pintype "bidirectional"))
    )
    (net (code "39") (name "Net-(ARDUINO-NANO1-PadTX1)") (class "Default")
      (node (ref "ARDUINO-NANO1") (pin "TX1") (pinfunction "TX1_TX1") (pintype "output"))
      (node (ref "PIN22") (pin "PIN1") (pinfunction "PIN1_PIN1") (pintype "bidirectional"))
    )
    (net (code "40") (name "Net-(D1-PadA)") (class "Default")
      (node (ref "D1") (pin "A") (pinfunction "A_A") (pintype "passive"))
      (node (ref "LED1") (pin "C") (pinfunction "C_C") (pintype "passive"))
      (node (ref "RLS1") (pin "A2") (pinfunction "A2_A2") (pintype "bidirectional"))
      (node (ref "T3") (pin "C") (pinfunction "C_C") (pintype "passive"))
    )
    (net (code "41") (name "Net-(D2-PadA)") (class "Default")
      (node (ref "D2") (pin "A") (pinfunction "A_A") (pintype "passive"))
      (node (ref "LED2") (pin "C") (pinfunction "C_C") (pintype "passive"))
      (node (ref "RLS2") (pin "A2") (pinfunction "A2_A2") (pintype "bidirectional"))
      (node (ref "T4") (pin "C") (pinfunction "C_C") (pintype "passive"))
    )
    (net (code "42") (name "Net-(D3-PadC)") (class "Default")
      (node (ref "D3") (pin "C") (pinfunction "C_C") (pintype "passive"))
      (node (ref "D4") (pin "A") (pinfunction "A_A") (pintype "passive"))
    )
    (net (code "43") (name "Net-(D5-PadC)") (class "Default")
      (node (ref "D5") (pin "C") (pinfunction "C_C") (pintype "passive"))
      (node (ref "D6") (pin "A") (pinfunction "A_A") (pintype "passive"))
    )
    (net (code "44") (name "Net-(D7-PadC)") (class "Default")
      (node (ref "D7") (pin "C") (pinfunction "C_C") (pintype "passive"))
      (node (ref "D8") (pin "A") (pinfunction "A_A") (pintype "passive"))
    )
    (net (code "45") (name "Net-(D11-PadA)") (class "Default")
      (node (ref "D11") (pin "A") (pinfunction "A_A") (pintype "passive"))
      (node (ref "D12") (pin "C") (pinfunction "C_C") (pintype "passive"))
    )
    (net (code "46") (name "Net-(D13-PadA)") (class "Default")
      (node (ref "D13") (pin "A") (pinfunction "A_A") (pintype "passive"))
      (node (ref "D14") (pin "C") (pinfunction "C_C") (pintype "passive"))
    )
    (net (code "47") (name "Net-(D15-PadA)") (class "Default")
      (node (ref "D15") (pin "A") (pinfunction "A_A") (pintype "passive"))
      (node (ref "D16") (pin "C") (pinfunction "C_C") (pintype "passive"))
    )
    (net (code "48") (name "Net-(IC1-VI)") (class "Default")
      (node (ref "C3") (pin "1") (pinfunction "1_1") (pintype "passive"))
      (node (ref "D17") (pin "C") (pinfunction "C_C") (pintype "passive"))
      (node (ref "D9") (pin "C") (pinfunction "C_C") (pintype "passive"))
      (node (ref "FU1") (pin "1") (pinfunction "1_1") (pintype "passive"))
      (node (ref "FU2") (pin "1") (pinfunction "1_1") (pintype "passive"))
      (node (ref "FU3") (pin "1") (pinfunction "1_1") (pintype "passive"))
      (node (ref "IC1") (pin "1") (pinfunction "VI_1") (pintype "input"))
    )
    (net (code "49") (name "Net-(LED1-PadA)") (class "Default")
      (node (ref "LED1") (pin "A") (pinfunction "A_A") (pintype "passive"))
      (node (ref "R15") (pin "1") (pinfunction "1_1") (pintype "passive"))
    )
    (net (code "50") (name "Net-(LED2-PadA)") (class "Default")
      (node (ref "LED2") (pin "A") (pinfunction "A_A") (pintype "passive"))
      (node (ref "R16") (pin "1") (pinfunction "1_1") (pintype "passive"))
    )
    (net (code "51") (name "Net-(LED3-PadA)") (class "Default")
      (node (ref "LED3") (pin "A") (pinfunction "A_A") (pintype "passive"))
      (node (ref "LED5") (pin "C") (pinfunction "C_C") (pintype "passive"))
      (node (ref "R19") (pin "1") (pinfunction "1_1") (pintype "passive"))
    )
    (net (code "52") (name "Net-(LED4-PadA)") (class "Default")
      (node (ref "LED4") (pin "A") (pinfunction "A_A") (pintype "passive"))
      (node (ref "LED6") (pin "C") (pinfunction "C_C") (pintype "passive"))
      (node (ref "R18") (pin "1") (pinfunction "1_1") (pintype "passive"))
    )
    (net (code "53") (name "Net-(LED7-PadA)") (class "Default")
      (node (ref "LED7") (pin "A") (pinfunction "A_A") (pintype "passive"))
      (node (ref "R31") (pin "1") (pinfunction "1_1") (pintype "passive"))
    )
    (net (code "54") (name "Net-(LED8-PadA)") (class "Default")
      (node (ref "LED8") (pin "A") (pinfunction "A_A") (pintype "passive"))
      (node (ref "R32") (pin "1") (pinfunction "1_1") (pintype "passive"))
    )
    (net (code "55") (name "Net-(LED9-PadA)") (class "Default")
      (node (ref "LED9") (pin "A") (pinfunction "A_A") (pintype "passive"))
      (node (ref "R30") (pin "1") (pinfunction "1_1") (pintype "passive"))
    )
    (net (code "56") (name "Net-(OK1-Pad1)") (class "Default")
      (node (ref "OK1") (pin "1") (pinfunction "1_1") (pintype "bidirectional"))
      (node (ref "OK2") (pin "2") (pinfunction "2_2") (pintype "bidirectional"))
      (node (ref "R24") (pin "2") (pinfunction "2_2") (pintype "passive"))
    )
    (net (code "57") (name "Net-(OK3-Pad1)") (class "Default")
      (node (ref "OK3") (pin "1") (pinfunction "1_1") (pintype "bidirectional"))
      (node (ref "OK4") (pin "2") (pinfunction "2_2") (pintype "bidirectional"))
      (node (ref "R25") (pin "2") (pinfunction "2_2") (pintype "passive"))
    )
    (net (code "58") (name "Net-(OK5-Pad1)") (class "Default")
      (node (ref "OK5") (pin "1") (pinfunction "1_1") (pintype "bidirectional"))
      (node (ref "OK6") (pin "2") (pinfunction "2_2") (pintype "bidirectional"))
      (node (ref "R26") (pin "2") (pinfunction "2_2") (pintype "passive"))
    )
    (net (code "59") (name "Net-(PIN1-PadPIN1)") (class "Default")
      (node (ref "PIN1") (pin "PIN1") (pinfunction "PIN1_PIN1") (pintype "bidirectional"))
      (node (ref "R7") (pin "1") (pinfunction "1_1") (pintype "passive"))
    )
    (net (code "60") (name "Net-(PIN3-PadPIN1)") (class "Default")
      (node (ref "PIN3") (pin "PIN1") (pinfunction "PIN1_PIN1") (pintype "bidirectional"))
      (node (ref "R9") (pin "1") (pinfunction "1_1") (pintype "passive"))
    )
    (net (code "61") (name "Net-(PIN4-PadPIN1)") (class "Default")
      (node (ref "PIN4") (pin "PIN1") (pinfunction "PIN1_PIN1") (pintype "bidirectional"))
      (node (ref "R10") (pin "1") (pinfunction "1_1") (pintype "passive"))
    )
    (net (code "62") (name "Net-(PIN6-PadPIN1)") (class "Default")
      (node (ref "PIN6") (pin "PIN1") (pinfunction "PIN1_PIN1") (pintype "bidirectional"))
      (node (ref "R12") (pin "1") (pinfunction "1_1") (pintype "passive"))
    )
    (net (code "63") (name "Net-(R1-Pad2)") (class "Default")
      (node (ref "R1") (pin "2") (pinfunction "2_2") (pintype "passive"))
      (node (ref "R3") (pin "2") (pinfunction "2_2") (pintype "passive"))
      (node (ref "T1") (pin "B") (pinfunction "B_B") (pintype "passive"))
    )
    (net (code "64") (name "Net-(R2-Pad2)") (class "Default")
      (node (ref "R2") (pin "2") (pinfunction "2_2") (pintype "passive"))
      (node (ref "R4") (pin "2") (pinfunction "2_2") (pintype "passive"))
      (node (ref "T2") (pin "B") (pinfunction "B_B") (pintype "passive"))
    )
    (net (code "65") (name "Net-(R13-Pad2)") (class "Default")
      (node (ref "R13") (pin "2") (pinfunction "2_2") (pintype "passive"))
      (node (ref "R17") (pin "2") (pinfunction "2_2") (pintype "passive"))
      (node (ref "T3") (pin "B") (pinfunction "B_B") (pintype "passive"))
    )
    (net (code "66") (name "Net-(R14-Pad2)") (class "Default")
      (node (ref "R14") (pin "2") (pinfunction "2_2") (pintype "passive"))
      (node (ref "R20") (pin "2") (pinfunction "2_2") (pintype "passive"))
      (node (ref "T4") (pin "B") (pinfunction "B_B") (pintype "passive"))
    )
    (net (code "67") (name "PN1_LED+") (class "Default")
      (node (ref "PIN16") (pin "PIN1") (pinfunction "PIN1_PIN1") (pintype "bidirectional"))
      (node (ref "R5") (pin "2") (pinfunction "2_2") (pintype "passive"))
    )
    (net (code "68") (name "PN1_LED-") (class "Default")
      (node (ref "PIN17") (pin "PIN1") (pinfunction "PIN1_PIN1") (pintype "bidirectional"))
      (node (ref "T1") (pin "C") (pinfunction "C_C") (pintype "passive"))
    )
    (net (code "69") (name "PN2_LED+") (class "Default")
      (node (ref "PIN20") (pin "PIN1") (pinfunction "PIN1_PIN1") (pintype "bidirectional"))
      (node (ref "R6") (pin "2") (pinfunction "2_2") (pintype "passive"))
    )
    (net (code "70") (name "PN2_LED-") (class "Default")
      (node (ref "PIN21") (pin "PIN1") (pinfunction "PIN1_PIN1") (pintype "bidirectional"))
      (node (ref "T2") (pin "C") (pinfunction "C_C") (pintype "passive"))
    )
    (net (code "71") (name "RAIL+") (class "Default")
      (node (ref "D12") (pin "A") (pinfunction "A_A") (pintype "passive"))
      (node (ref "D14") (pin "A") (pinfunction "A_A") (pintype "passive"))
      (node (ref "D16") (pin "A") (pinfunction "A_A") (pintype "passive"))
      (node (ref "D4") (pin "C") (pinfunction "C_C") (pintype "passive"))
      (node (ref "D6") (pin "C") (pinfunction "C_C") (pintype "passive"))
      (node (ref "D8") (pin "C") (pinfunction "C_C") (pintype "passive"))
      (node (ref "OK1") (pin "2") (pinfunction "2_2") (pintype "bidirectional"))
      (node (ref "OK2") (pin "1") (pinfunction "1_1") (pintype "bidirectional"))
      (node (ref "OK3") (pin "2") (pinfunction "2_2") (pintype "bidirectional"))
      (node (ref "OK4") (pin "1") (pinfunction "1_1") (pintype "bidirectional"))
      (node (ref "OK5") (pin "2") (pinfunction "2_2") (pintype "bidirectional"))
      (node (ref "OK6") (pin "1") (pinfunction "1_1") (pintype "bidirectional"))
      (node (ref "PIN10") (pin "PIN1") (pinfunction "PIN1_PIN1") (pintype "bidirectional"))
      (node (ref "R21") (pin "1") (pinfunction "1_1") (pintype "passive"))
      (node (ref "R22") (pin "1") (pinfunction "1_1") (pintype "passive"))
      (node (ref "R23") (pin "1") (pinfunction "1_1") (pintype "passive"))
    )
    (net (code "72") (name "RAIL-") (class "Default")
      (node (ref "PIN11") (pin "PIN1") (pinfunction "PIN1_PIN1") (pintype "bidirectional"))
    )
    (net (code "73") (name "TRANSPORT") (class "Default")
      (node (ref "ARDUINO-NANO1") (pin "A1") (pinfunction "A1_A1") (pintype "bidirectional"))
      (node (ref "PIN2") (pin "PIN1") (pinfunction "PIN1_PIN1") (pintype "bidirectional"))
      (node (ref "R8") (pin "1") (pinfunction "1_1") (pintype "passive"))
    )
    (net (code "74") (name "unconnected-(ARDUINO-NANO1-PadRST1)") (class "Default")
      (node (ref "ARDUINO-NANO1") (pin "RST1") (pinfunction "RST1_RST1") (pintype "input"))
    )
    (net (code "75") (name "unconnected-(ARDUINO-NANO1-PadRST2)") (class "Default")
      (node (ref "ARDUINO-NANO1") (pin "RST2") (pinfunction "RST2_RST2") (pintype "bidirectional"))
    )
  )
)
